# Sheet1.net
KiCad netlist of a schematic drawn in Altium Designer
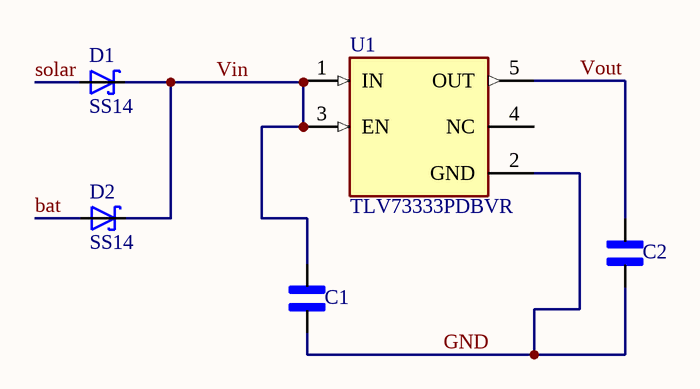
[diagram p0: Sheet1.SchDoc]

(export (version "E")
  (design (tool "Eeschema 10.0.6"))
  (components
    (comp (ref "C1")
      (value "FS051C473K4Z2A")
      (footprint "CAPC2012X140N")
      (description "Ceramic Capacitor")
      (fields (field (name "MF") "AVX"))
      (libsource (lib "SMD Capacitor") (part "FS051C473K4Z2A"))
    )
    (comp (ref "C2")
      (value "FS051C473K4Z2A")
      (footprint "CAPC2012X140N")
      (description "Ceramic Capacitor")
      (fields (field (name "MF") "AVX"))
      (libsource (lib "SMD Capacitor") (part "FS051C473K4Z2A"))
    )
    (comp (ref "D1")
      (value "SS14")
      (footprint "DO-214AC")
      (description "Diode Schottky 40 V 1A Surface Mount DO-214AC (SMA)")
      (fields (field (name "MF") "onsemi"))
      (libsource (lib "SS14_SMA_2040") (part "SS14"))
    )
    (comp (ref "D2")
      (value "SS14")
      (footprint "DO-214AC")
      (description "Diode Schottky 40 V 1A Surface Mount DO-214AC (SMA)")
      (fields (field (name "MF") "onsemi"))
      (libsource (lib "SS14_SMA_2040") (part "SS14"))
    )
    (comp (ref "U1")
      (value "TLV73333PDBVR")
      (footprint "SOT95P280X145-5N")
      (description "300-mA, capacitor-free, low-IQ, low-dropout voltage regulator with enable")
      (fields (field (name "MF") "Texas Instruments"))
      (libsource (lib "TLV73333PDBVR") (part "TLV73333PDBVR"))
    )
  )
  (nets
    (net (code "1") (name "/GND") (class "Default")
      (node (ref "C1") (pin "2") (pinfunction "2_2") (pintype "passive"))
      (node (ref "C2") (pin "2") (pinfunction "2_2") (pintype "passive"))
      (node (ref "U1") (pin "2") (pinfunction "GND_2") (pintype "power_in"))
    )
    (net (code "2") (name "/Vin") (class "Default")
      (node (ref "C1") (pin "1") (pinfunction "1_1") (pintype "passive"))
      (node (ref "D1") (pin "K") (pinfunction "K_K") (pintype "passive"))
      (node (ref "D2") (pin "K") (pinfunction "K_K") (pintype "passive"))
      (node (ref "U1") (pin "1") (pinfunction "IN_1") (pintype "input"))
      (node (ref "U1") (pin "3") (pinfunction "EN_3") (pintype "input"))
    )
    (net (code "3") (name "/Vout") (class "Default")
      (node (ref "C2") (pin "1") (pinfunction "1_1") (pintype "passive"))
      (node (ref "U1") (pin "5") (pinfunction "OUT_5") (pintype "output"))
    )
    (net (code "4") (name "/bat") (class "Default")
      (node (ref "D2") (pin "A") (pinfunction "A_A") (pintype "passive"))
    )
    (net (code "5") (name "/solar") (class "Default")
      (node (ref "D1") (pin "A") (pinfunction "A_A") (pintype "passive"))
    )
    (net (code "6") (name "unconnected-(U1-NC-Pad4)") (class "Default")
      (node (ref "U1") (pin "4") (pinfunction "NC_4") (pintype "passive"))
    )
  )
)
